# Serializer_DS90UB913A.net
KiCad netlist of a schematic drawn in Altium Designer
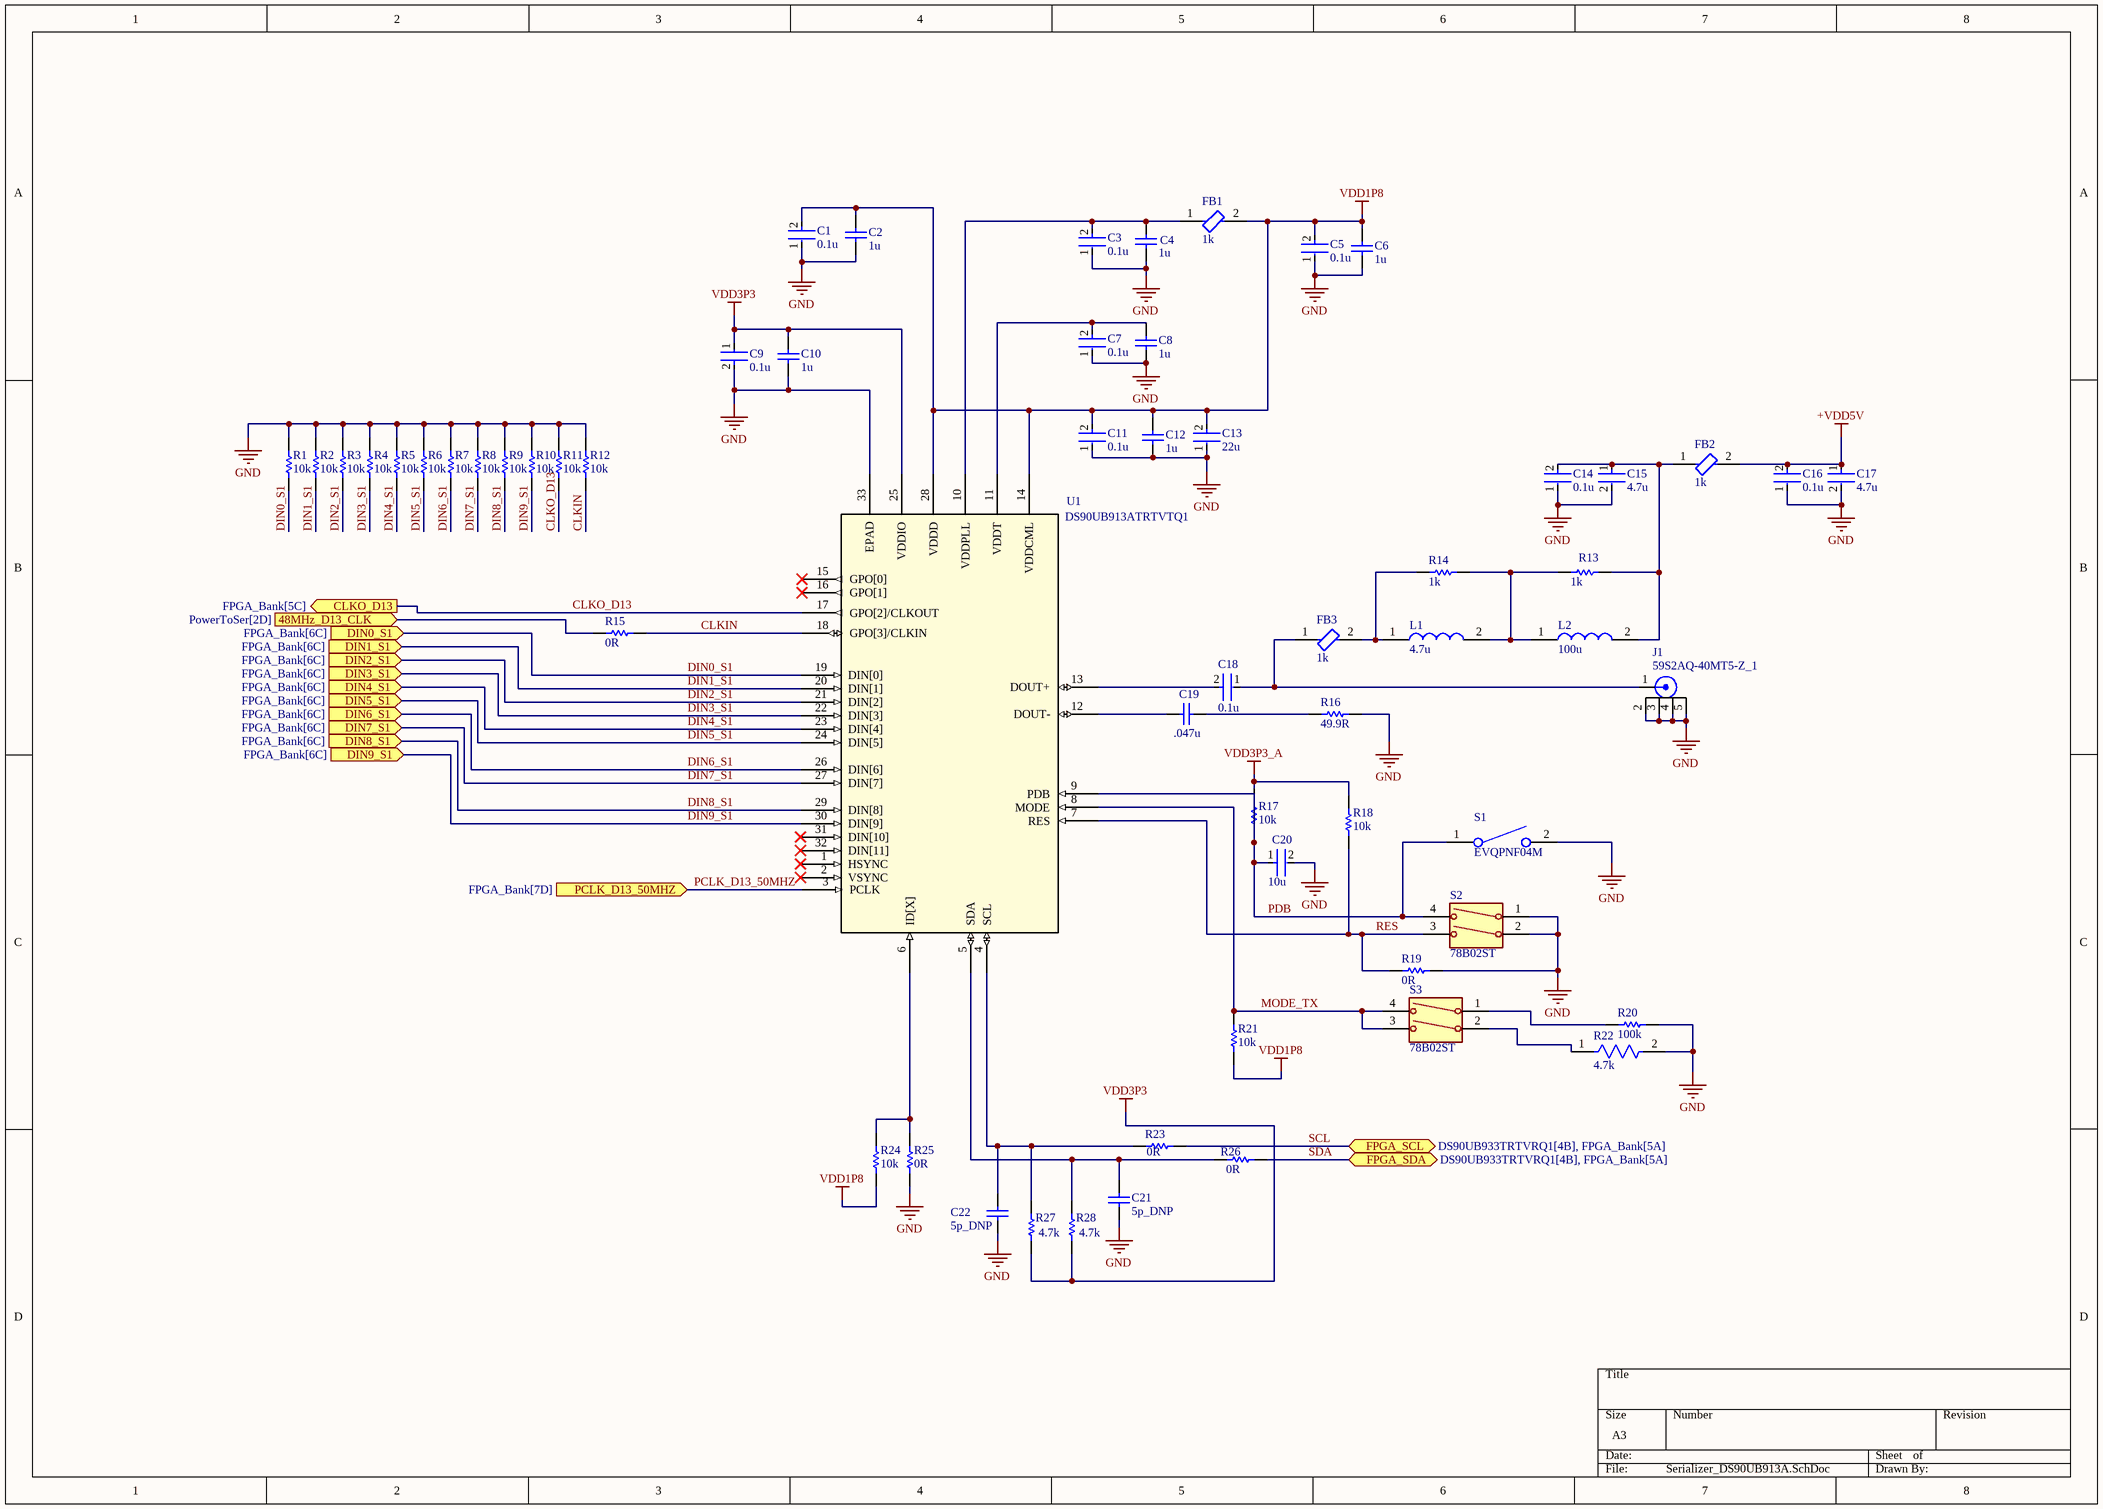
[diagram p0: Serializer_DS90UB913A.SchDoc]

(export (version "E")
  (design (tool "Eeschema 10.0.6"))
  (components
    (comp (ref "C1")
      (value "0.1u")
      (footprint "FP-GRM15-MFG")
      (description "CAP CER 0.1UF 16V X7R 0402")
      (fields (field (name "MANUFACTURER PART NUMBER") "GRM155R71C104KA88D") (field (name "TOLERANCE") "10%"))
      (libsource (lib "Altium Content Vault") (part "236180d848d6139a670b325ea6854c9"))
    )
    (comp (ref "C2")
      (value "1u")
      (footprint "CAPC1608X90X35ML10T15")
      (fields (field (name "MANUFACTURER") "Murata") (field (name "PART NUMBER") "GRM188R71E105KA12D"))
      (libsource (lib "Altium Content Vault") (part "CAP"))
    )
    (comp (ref "C3")
      (value "0.1u")
      (footprint "FP-GRM15-MFG")
      (description "CAP CER 0.1UF 16V X7R 0402")
      (fields (field (name "MANUFACTURER PART NUMBER") "GRM155R71C104KA88D") (field (name "TOLERANCE") "10%"))
      (libsource (lib "Altium Content Vault") (part "236180d848d6139a670b325ea6854c9"))
    )
    (comp (ref "C4")
      (value "1u")
      (footprint "CAPC1608X90X35ML10T15")
      (fields (field (name "MANUFACTURER") "Murata") (field (name "PART NUMBER") "GRM188R71E105KA12D"))
      (libsource (lib "Altium Content Vault") (part "CAP"))
    )
    (comp (ref "C5")
      (value "0.1u")
      (footprint "FP-GRM15-MFG")
      (description "CAP CER 0.1UF 16V X7R 0402")
      (fields (field (name "MANUFACTURER PART NUMBER") "GRM155R71C104KA88D") (field (name "TOLERANCE") "10%"))
      (libsource (lib "Altium Content Vault") (part "236180d848d6139a670b325ea6854c9"))
    )
    (comp (ref "C6")
      (value "1u")
      (footprint "CAPC1608X90X35ML10T15")
      (fields (field (name "MANUFACTURER") "Murata") (field (name "PART NUMBER") "GRM188R71E105KA12D"))
      (libsource (lib "Altium Content Vault") (part "CAP"))
    )
    (comp (ref "C7")
      (value "0.1u")
      (footprint "FP-GRM15-MFG")
      (description "CAP CER 0.1UF 16V X7R 0402")
      (fields (field (name "MANUFACTURER PART NUMBER") "GRM155R71C104KA88D") (field (name "TOLERANCE") "10%"))
      (libsource (lib "Altium Content Vault") (part "236180d848d6139a670b325ea6854c9"))
    )
    (comp (ref "C8")
      (value "1u")
      (footprint "CAPC1608X90X35ML10T15")
      (fields (field (name "MANUFACTURER") "Murata") (field (name "PART NUMBER") "GRM188R71E105KA12D"))
      (libsource (lib "Altium Content Vault") (part "CAP"))
    )
    (comp (ref "C9")
      (value "0.1u")
      (footprint "FP-GRM15-MFG")
      (description "CAP CER 0.1UF 16V X7R 0402")
      (fields (field (name "MANUFACTURER PART NUMBER") "GRM155R71C104KA88D") (field (name "TOLERANCE") "10%"))
      (libsource (lib "Altium Content Vault") (part "236180d848d6139a670b325ea6854c9"))
    )
    (comp (ref "C10")
      (value "1u")
      (footprint "CAPC1608X90X35ML10T15")
      (fields (field (name "MANUFACTURER") "Murata") (field (name "PART NUMBER") "GRM188R71E105KA12D"))
      (libsource (lib "Altium Content Vault") (part "CAP"))
    )
    (comp (ref "C11")
      (value "0.1u")
      (footprint "FP-GRM15-MFG")
      (description "CAP CER 0.1UF 16V X7R 0402")
      (fields (field (name "MANUFACTURER PART NUMBER") "GRM155R71C104KA88D") (field (name "TOLERANCE") "10%"))
      (libsource (lib "Altium Content Vault") (part "236180d848d6139a670b325ea6854c9"))
    )
    (comp (ref "C12")
      (value "1u")
      (footprint "CAPC1608X90X35ML10T15")
      (fields (field (name "MANUFACTURER") "Murata") (field (name "PART NUMBER") "GRM188R71E105KA12D"))
      (libsource (lib "Altium Content Vault") (part "CAP"))
    )
    (comp (ref "C13")
      (value "22u")
      (footprint "FP-GCM32E-0_3-IPC_B")
      (description "Ceramic Capacitor for Automotive 22uF ±10% 16VDC X7R 1210 Embossed T/R")
      (fields (field (name "VOLTAGE") "16V") (field (name "TOLERANCE") "10%"))
      (libsource (lib "Altium Content Vault") (part "f23184f103b6ebe33a8c269c53dcba6"))
    )
    (comp (ref "C14")
      (value "0.1u")
      (footprint "FP-GRM15-MFG")
      (description "CAP CER 0.1UF 16V X7R 0402")
      (fields (field (name "MANUFACTURER PART NUMBER") "GRM155R71C104KA88D") (field (name "TOLERANCE") "10%"))
      (libsource (lib "Altium Content Vault") (part "236180d848d6139a670b325ea6854c9"))
    )
    (comp (ref "C15")
      (value "4.7u")
      (footprint "FP-GRM21B-0_15-MFG")
      (description "CAP CER 4.7UF 16V X7R 0805")
      (fields (field (name "VOLTAGE") "16V") (field (name "TOLERANCE") "10%"))
      (libsource (lib "Altium Content Vault") (part "b4654b650e69147ec39a6b967a45e02"))
    )
    (comp (ref "C16")
      (value "0.1u")
      (footprint "FP-GRM15-MFG")
      (description "CAP CER 0.1UF 16V X7R 0402")
      (fields (field (name "MANUFACTURER PART NUMBER") "GRM155R71C104KA88D") (field (name "TOLERANCE") "10%"))
      (libsource (lib "Altium Content Vault") (part "236180d848d6139a670b325ea6854c9"))
    )
    (comp (ref "C17")
      (value "4.7u")
      (footprint "FP-GRM21B-0_15-MFG")
      (description "CAP CER 4.7UF 16V X7R 0805")
      (fields (field (name "VOLTAGE") "16V") (field (name "TOLERANCE") "10%"))
      (libsource (lib "Altium Content Vault") (part "b4654b650e69147ec39a6b967a45e02"))
    )
    (comp (ref "C18")
      (value "0.1u")
      (footprint "FP-GRM15-MFG")
      (description "CAP CER 0.1UF 16V X7R 0402")
      (fields (field (name "MANUFACTURER PART NUMBER") "GRM155R71C104KA88D") (field (name "TOLERANCE") "10%"))
      (libsource (lib "Altium Content Vault") (part "236180d848d6139a670b325ea6854c9"))
    )
    (comp (ref "C19")
      (value ".047u")
      (footprint "CAPC1608X90X35ML10T15")
      (fields (field (name "MANUFACTURER") "Murata") (field (name "PART NUMBER") "GRM188R71H473KA61D"))
      (libsource (lib "Altium Content Vault") (part "CAP"))
    )
    (comp (ref "C20")
      (value "10u")
      (footprint "FP-GRM21B-0_1-IPC_C")
      (description "Chip Multilayer Ceramic Capacitors for General Purpose, 0805, 10uF, X5R, 15%, 10%, 16V")
      (fields (field (name "TOLERANCE") "10%") (field (name "VOLTAGE") "16V"))
      (libsource (lib "Altium Content Vault") (part "b4654b650e69147ec39a6b967a45e02"))
    )
    (comp (ref "C21")
      (value "5p_DNP")
      (footprint "CAPC1005X55X25LL05T10")
      (fields (field (name "MANUFACTURER") "Murata") (field (name "PART NUMBER") "GRM1555C1H5R0CA01D"))
      (libsource (lib "Altium Content Vault") (part "CAP"))
    )
    (comp (ref "C22")
      (value "5p_DNP")
      (footprint "CAPC1005X55X25LL05T10")
      (fields (field (name "MANUFACTURER") "Murata") (field (name "PART NUMBER") "GRM1555C1H5R0CA01D"))
      (libsource (lib "Altium Content Vault") (part "CAP"))
    )
    (comp (ref "FB1")
      (value "1k")
      (footprint "FP-BLM18-0_15-t0_8-MFG")
      (description "Chip Ferrite Bead, 0603, 1000Ω @ 100MHz, 0.5Ω, 25%, 450mABLM18AG102SN1D")
      (fields (field (name "TOLERANCE") "25%"))
      (libsource (lib "Altium Content Vault") (part "5f30dd21d616792df468990f7003faa"))
    )
    (comp (ref "FB2")
      (value "1k")
      (footprint "FP-BLM18-0_15-t0_8-MFG")
      (description "Chip Ferrite Bead, 0603, 1000Ω @ 100MHz, 0.5Ω, 25%, 450mABLM18AG102SN1D")
      (fields (field (name "TOLERANCE") "25%"))
      (libsource (lib "Altium Content Vault") (part "5f30dd21d616792df468990f7003faa"))
    )
    (comp (ref "FB3")
      (value "1k")
      (footprint "FP-BLM18-0_15-t0_8-MFG")
      (description "Chip Ferrite Bead, 0603, 1000Ω @ 100MHz, 0.5Ω, 25%, 450mABLM18AG102SN1D")
      (fields (field (name "TOLERANCE") "25%"))
      (libsource (lib "Altium Content Vault") (part "5f30dd21d616792df468990f7003faa"))
    )
    (comp (ref "J1")
      (value "59S2AQ-40MT5-Z_1")
      (footprint "SerDes_Eval_Board_Footprints:ROSENBERGER_59S2AQ-40MT5-Z_1")
      (description "RF Connectors / Coaxial Connectors Plug PC-Board SMD Right AngleZWatrBlue")
      (libsource (lib "SerDes_Eval") (part "59S2AQ-40MT5-Z_1"))
    )
    (comp (ref "L1")
      (value "4.7u")
      (footprint "SerDes_Eval_Board_Footprints:1008PS")
      (description "Inductor")
      (fields
        (field (name "MANUFACTURER_PART_NUMBER") "1008PS-472KLB")
        (field (name "MOUSER PART NUMBER") "994-1008PS-472KLB")
      )
      (libsource (lib "SerDes_Eval") (part "1008PS-472KLB"))
    )
    (comp (ref "L2")
      (value "100u")
      (footprint "SerDes_Eval_Board_Footprints:MSS7341T104MLB")
      (description "Inductor")
      (fields
        (field (name "MANUFACTURER_PART_NUMBER") "MSS7341T-104MLD")
        (field (name "MOUSER PART NUMBER") "994-MSS7341T-104MLD")
      )
      (libsource (lib "SerDes_Eval") (part "MSS7341T-104MLB"))
    )
    (comp (ref "R1")
      (value "10k")
      (footprint "RESC1005X40X25ML05T05")
      (fields (field (name "PART NUMBER") "ERJ-2GEJ103X") (field (name "MANUFACTURER") "Panasonic"))
      (libsource (lib "Altium Content Vault") (part "RES"))
    )
    (comp (ref "R2")
      (value "10k")
      (footprint "RESC1005X40X25ML05T05")
      (fields (field (name "PART NUMBER") "ERJ-2GEJ103X") (field (name "MANUFACTURER") "Panasonic"))
      (libsource (lib "Altium Content Vault") (part "RES"))
    )
    (comp (ref "R3")
      (value "10k")
      (footprint "RESC1005X40X25ML05T05")
      (fields (field (name "PART NUMBER") "ERJ-2GEJ103X") (field (name "MANUFACTURER") "Panasonic"))
      (libsource (lib "Altium Content Vault") (part "RES"))
    )
    (comp (ref "R4")
      (value "10k")
      (footprint "RESC1005X40X25ML05T05")
      (fields (field (name "PART NUMBER") "ERJ-2GEJ103X") (field (name "MANUFACTURER") "Panasonic"))
      (libsource (lib "Altium Content Vault") (part "RES"))
    )
    (comp (ref "R5")
      (value "10k")
      (footprint "RESC1005X40X25ML05T05")
      (fields (field (name "PART NUMBER") "ERJ-2GEJ103X") (field (name "MANUFACTURER") "Panasonic"))
      (libsource (lib "Altium Content Vault") (part "RES"))
    )
    (comp (ref "R6")
      (value "10k")
      (footprint "RESC1005X40X25ML05T05")
      (fields (field (name "PART NUMBER") "ERJ-2GEJ103X") (field (name "MANUFACTURER") "Panasonic"))
      (libsource (lib "Altium Content Vault") (part "RES"))
    )
    (comp (ref "R7")
      (value "10k")
      (footprint "RESC1005X40X25ML05T05")
      (fields (field (name "PART NUMBER") "ERJ-2GEJ103X") (field (name "MANUFACTURER") "Panasonic"))
      (libsource (lib "Altium Content Vault") (part "RES"))
    )
    (comp (ref "R8")
      (value "10k")
      (footprint "RESC1005X40X25ML05T05")
      (fields (field (name "PART NUMBER") "ERJ-2GEJ103X") (field (name "MANUFACTURER") "Panasonic"))
      (libsource (lib "Altium Content Vault") (part "RES"))
    )
    (comp (ref "R9")
      (value "10k")
      (footprint "RESC1005X40X25ML05T05")
      (fields (field (name "PART NUMBER") "ERJ-2GEJ103X") (field (name "MANUFACTURER") "Panasonic"))
      (libsource (lib "Altium Content Vault") (part "RES"))
    )
    (comp (ref "R10")
      (value "10k")
      (footprint "RESC1005X40X25ML05T05")
      (fields (field (name "PART NUMBER") "ERJ-2GEJ103X") (field (name "MANUFACTURER") "Panasonic"))
      (libsource (lib "Altium Content Vault") (part "RES"))
    )
    (comp (ref "R11")
      (value "10k")
      (footprint "RESC1005X40X25ML05T05")
      (fields (field (name "PART NUMBER") "ERJ-2GEJ103X") (field (name "MANUFACTURER") "Panasonic"))
      (libsource (lib "Altium Content Vault") (part "RES"))
    )
    (comp (ref "R12")
      (value "10k")
      (footprint "RESC1005X40X25ML05T05")
      (fields (field (name "PART NUMBER") "ERJ-2GEJ103X") (field (name "MANUFACTURER") "Panasonic"))
      (libsource (lib "Altium Content Vault") (part "RES"))
    )
    (comp (ref "R13")
      (value "1k")
      (footprint "RESC1608X55X30LL15T15")
      (fields (field (name "PART NUMBER") "ERJ-3EKF1001V") (field (name "MANUFACTURER") "Panasonic"))
      (libsource (lib "Altium Content Vault") (part "RES"))
    )
    (comp (ref "R14")
      (value "1k")
      (footprint "RESC1608X55X30LL15T15")
      (fields (field (name "PART NUMBER") "ERJ-3EKF1001V") (field (name "MANUFACTURER") "Panasonic"))
      (libsource (lib "Altium Content Vault") (part "RES"))
    )
    (comp (ref "R15")
      (value "0R")
      (footprint "RESC1005X40X25LL05T05")
      (description "Chip Resistor, 0 Ohm, 0.1 W, -55 to 155 degC, 0402 (1005 Metric), RoHS, Tape and Reel")
      (fields (field (name "MANUFACTURER") "Panasonic") (field (name "TOLERANCE") "5%"))
      (libsource (lib "Altium Content Vault") (part "RES-2"))
    )
    (comp (ref "R16")
      (value "49.9R")
      (footprint "RESC1608X55X30ML15T15")
      (fields (field (name "MANUFACTURER") "Panasonic") (field (name "PART NUMBER") "ERJ-3EKF49R9V"))
      (libsource (lib "Altium Content Vault") (part "RES"))
    )
    (comp (ref "R17")
      (value "10k")
      (footprint "RESC1005X40X25ML05T05")
      (fields (field (name "PART NUMBER") "ERJ-2GEJ103X") (field (name "MANUFACTURER") "Panasonic"))
      (libsource (lib "Altium Content Vault") (part "RES"))
    )
    (comp (ref "R18")
      (value "10k")
      (footprint "RESC1005X40X25ML05T05")
      (fields (field (name "PART NUMBER") "ERJ-2GEJ103X") (field (name "MANUFACTURER") "Panasonic"))
      (libsource (lib "Altium Content Vault") (part "RES"))
    )
    (comp (ref "R19")
      (value "0R")
      (footprint "RESC1005X40X25LL05T05")
      (description "Chip Resistor, 0 Ohm, 0.1 W, -55 to 155 degC, 0402 (1005 Metric), RoHS, Tape and Reel")
      (fields (field (name "MANUFACTURER") "Panasonic") (field (name "TOLERANCE") "5%"))
      (libsource (lib "Altium Content Vault") (part "RES-2"))
    )
    (comp (ref "R20")
      (value "100k")
      (footprint "RESC2013X70X40ML20T20")
      (fields (field (name "PART NUMBER") "ERJ-6ENF1003V") (field (name "MANUFACTURER") "Panasonic"))
      (libsource (lib "Altium Content Vault") (part "RES"))
    )
    (comp (ref "R21")
      (value "10k")
      (footprint "RESC1005X40X25ML05T05")
      (fields (field (name "PART NUMBER") "ERJ-2GEJ103X") (field (name "MANUFACTURER") "Panasonic"))
      (libsource (lib "Altium Content Vault") (part "RES"))
    )
    (comp (ref "R22")
      (value "4.7k")
      (footprint "FP-ERJ6GE-MFG")
      (description "RES SMD 4.7K OHM 5% 1/8W 0805")
      (fields (field (name "TOLERANCE") "5%"))
      (libsource (lib "Altium Content Vault") (part "1029c3af85768c4190bb7ad29bc67b5"))
    )
    (comp (ref "R23")
      (value "0R")
      (footprint "RESC1005X40X25LL05T05")
      (description "Chip Resistor, 0 Ohm, 0.1 W, -55 to 155 degC, 0402 (1005 Metric), RoHS, Tape and Reel")
      (fields (field (name "MANUFACTURER") "Panasonic") (field (name "TOLERANCE") "5%"))
      (libsource (lib "Altium Content Vault") (part "RES-2"))
    )
    (comp (ref "R24")
      (value "10k")
      (footprint "RESC1005X40X25ML05T05")
      (fields (field (name "PART NUMBER") "ERJ-2GEJ103X") (field (name "MANUFACTURER") "Panasonic"))
      (libsource (lib "Altium Content Vault") (part "RES"))
    )
    (comp (ref "R25")
      (value "0R")
      (footprint "RESC1005X40X25LL05T05")
      (description "Chip Resistor, 0 Ohm, 0.1 W, -55 to 155 degC, 0402 (1005 Metric), RoHS, Tape and Reel")
      (fields (field (name "MANUFACTURER") "Panasonic") (field (name "TOLERANCE") "5%"))
      (libsource (lib "Altium Content Vault") (part "RES-2"))
    )
    (comp (ref "R26")
      (value "0R")
      (footprint "RESC1005X40X25LL05T05")
      (description "Chip Resistor, 0 Ohm, 0.1 W, -55 to 155 degC, 0402 (1005 Metric), RoHS, Tape and Reel")
      (fields (field (name "MANUFACTURER") "Panasonic") (field (name "TOLERANCE") "5%"))
      (libsource (lib "Altium Content Vault") (part "RES-2"))
    )
    (comp (ref "R27")
      (value "4.7k")
      (footprint "RESC1005X40X25LL05T05")
      (description "Chip Resistor, 4.7 KOhm, +/- 1%, 0.1 W, -55 to 155 degC, 0402 (1005 Metric), RoHS, Tape and Reel")
      (fields (field (name "TOLERANCE") "1%") (field (name "PARTNUMBER") "ERJ-2RKF4701X"))
      (libsource (lib "Altium Content Vault") (part "RES-2"))
    )
    (comp (ref "R28")
      (value "4.7k")
      (footprint "RESC1005X40X25LL05T05")
      (description "Chip Resistor, 4.7 KOhm, +/- 1%, 0.1 W, -55 to 155 degC, 0402 (1005 Metric), RoHS, Tape and Reel")
      (fields (field (name "TOLERANCE") "1%") (field (name "PARTNUMBER") "ERJ-2RKF4701X"))
      (libsource (lib "Altium Content Vault") (part "RES-2"))
    )
    (comp (ref "S1")
      (value "EVQPNF04M")
      (footprint "SamacSys:EVQ5PN05K")
      (description "Switch")
      (libsource (lib "SerDes_Eval") (part "EVQPNF04M"))
    )
    (comp (ref "S2")
      (value "78B02ST")
      (footprint "78B02ST")
      (description "PCB Slide Switch Single Pole Single Throw (SPST) 150 mA Slide")
      (fields (field (name "MOUSER PART NUMBER") "706-78B02ST"))
      (libsource (lib "SerDes_Eval") (part "78B02ST"))
    )
    (comp (ref "S3")
      (value "78B02ST")
      (footprint "78B02ST")
      (description "PCB Slide Switch Single Pole Single Throw (SPST) 150 mA Slide")
      (fields (field (name "MOUSER PART NUMBER") "706-78B02ST"))
      (libsource (lib "SerDes_Eval") (part "78B02ST"))
    )
    (comp (ref "U1")
      (value "DS90UB913ATRTVTQ1")
      (footprint "RTV32_3P1X3P1_TEX")
      (description "25- to 100-MHz, 10-bit & 12-bit FPD-Link III serializer 32-WQFN -40 to 105")
      (fields (field (name "COPYRIGHT") "Copyright (C) 2025 Ultra Librarian. All rights reserved."))
      (libsource (lib "SerDes_Eval") (part "DS90UB913ATRTVTQ1"))
    )
  )
  (nets
    (net (code "1") (name "+VDD5V") (class "Default")
      (node (ref "C16") (pin "2") (pinfunction "2_2") (pintype "passive"))
      (node (ref "C17") (pin "1") (pinfunction "1_1") (pintype "passive"))
      (node (ref "FB2") (pin "2") (pinfunction "2_2") (pintype "passive"))
    )
    (net (code "2") (name "/48MHz_D13_CLK") (class "Default")
      (node (ref "R15") (pin "2") (pinfunction "2_2") (pintype "passive"))
    )
    (net (code "3") (name "/CLKIN") (class "Default")
      (node (ref "R12") (pin "1") (pinfunction "1_1") (pintype "passive"))
      (node (ref "R15") (pin "1") (pinfunction "1_1") (pintype "passive"))
      (node (ref "U1") (pin "18") (pinfunction "GPO[3]/CLKIN_18") (pintype "bidirectional"))
    )
    (net (code "4") (name "/CLKO_D13") (class "Default")
      (node (ref "R11") (pin "1") (pinfunction "1_1") (pintype "passive"))
      (node (ref "U1") (pin "17") (pinfunction "GPO[2]/CLKOUT_17") (pintype "output"))
    )
    (net (code "5") (name "/DIN0_S1") (class "Default")
      (node (ref "R1") (pin "1") (pinfunction "1_1") (pintype "passive"))
      (node (ref "U1") (pin "19") (pinfunction "DIN[0]_19") (pintype "input"))
    )
    (net (code "6") (name "/DIN1_S1") (class "Default")
      (node (ref "R2") (pin "1") (pinfunction "1_1") (pintype "passive"))
      (node (ref "U1") (pin "20") (pinfunction "DIN[1]_20") (pintype "input"))
    )
    (net (code "7") (name "/DIN2_S1") (class "Default")
      (node (ref "R3") (pin "1") (pinfunction "1_1") (pintype "passive"))
      (node (ref "U1") (pin "21") (pinfunction "DIN[2]_21") (pintype "input"))
    )
    (net (code "8") (name "/DIN3_S1") (class "Default")
      (node (ref "R4") (pin "1") (pinfunction "1_1") (pintype "passive"))
      (node (ref "U1") (pin "22") (pinfunction "DIN[3]_22") (pintype "input"))
    )
    (net (code "9") (name "/DIN4_S1") (class "Default")
      (node (ref "R5") (pin "1") (pinfunction "1_1") (pintype "passive"))
      (node (ref "U1") (pin "23") (pinfunction "DIN[4]_23") (pintype "input"))
    )
    (net (code "10") (name "/DIN5_S1") (class "Default")
      (node (ref "R6") (pin "1") (pinfunction "1_1") (pintype "passive"))
      (node (ref "U1") (pin "24") (pinfunction "DIN[5]_24") (pintype "input"))
    )
    (net (code "11") (name "/DIN6_S1") (class "Default")
      (node (ref "R7") (pin "1") (pinfunction "1_1") (pintype "passive"))
      (node (ref "U1") (pin "26") (pinfunction "DIN[6]_26") (pintype "input"))
    )
    (net (code "12") (name "/DIN7_S1") (class "Default")
      (node (ref "R8") (pin "1") (pinfunction "1_1") (pintype "passive"))
      (node (ref "U1") (pin "27") (pinfunction "DIN[7]_27") (pintype "input"))
    )
    (net (code "13") (name "/DIN8_S1") (class "Default")
      (node (ref "R9") (pin "1") (pinfunction "1_1") (pintype "passive"))
      (node (ref "U1") (pin "29") (pinfunction "DIN[8]_29") (pintype "input"))
    )
    (net (code "14") (name "/DIN9_S1") (class "Default")
      (node (ref "R10") (pin "1") (pinfunction "1_1") (pintype "passive"))
      (node (ref "U1") (pin "30") (pinfunction "DIN[9]_30") (pintype "input"))
    )
    (net (code "15") (name "/MODE_TX") (class "Default")
      (node (ref "R21") (pin "2") (pinfunction "2_2") (pintype "passive"))
      (node (ref "S3") (pin "3") (pinfunction "COM_2_3") (pintype "passive"))
      (node (ref "S3") (pin "4") (pinfunction "NO_2_4") (pintype "passive"))
      (node (ref "U1") (pin "8") (pinfunction "MODE_8") (pintype "input"))
    )
    (net (code "16") (name "/PCLK_D13_50MHZ") (class "Default")
      (node (ref "U1") (pin "3") (pinfunction "PCLK_3") (pintype "input"))
    )
    (net (code "17") (name "/PDB") (class "Default")
      (node (ref "C20") (pin "1") (pinfunction "1_1") (pintype "passive"))
      (node (ref "R17") (pin "1") (pinfunction "1_1") (pintype "passive"))
      (node (ref "S1") (pin "1") (pinfunction "COM_1") (pintype "passive"))
      (node (ref "S2") (pin "4") (pinfunction "NO_2_4") (pintype "passive"))
      (node (ref "U1") (pin "9") (pinfunction "PDB_9") (pintype "input"))
    )
    (net (code "18") (name "/RES") (class "Default")
      (node (ref "R18") (pin "1") (pinfunction "1_1") (pintype "passive"))
      (node (ref "R19") (pin "2") (pinfunction "2_2") (pintype "passive"))
      (node (ref "S2") (pin "3") (pinfunction "COM_2_3") (pintype "passive"))
      (node (ref "U1") (pin "7") (pinfunction "RES_7") (pintype "input"))
    )
    (net (code "19") (name "/SCL") (class "Default")
      (node (ref "R23") (pin "1") (pinfunction "1_1") (pintype "passive"))
    )
    (net (code "20") (name "/SDA") (class "Default")
      (node (ref "R26") (pin "1") (pinfunction "1_1") (pintype "passive"))
    )
    (net (code "21") (name "GND") (class "Default")
      (node (ref "C1") (pin "1") (pinfunction "1_1") (pintype "passive"))
      (node (ref "C10") (pin "1") (pinfunction "1_1") (pintype "passive"))
      (node (ref "C11") (pin "1") (pinfunction "1_1") (pintype "passive"))
      (node (ref "C12") (pin "1") (pinfunction "1_1") (pintype "passive"))
      (node (ref "C13") (pin "1") (pinfunction "1_1") (pintype "passive"))
      (node (ref "C14") (pin "1") (pinfunction "1_1") (pintype "passive"))
      (node (ref "C15") (pin "2") (pinfunction "2_2") (pintype "passive"))
      (node (ref "C16") (pin "1") (pinfunction "1_1") (pintype "passive"))
      (node (ref "C17") (pin "2") (pinfunction "2_2") (pintype "passive"))
      (node (ref "C2") (pin "1") (pinfunction "1_1") (pintype "passive"))
      (node (ref "C20") (pin "2") (pinfunction "2_2") (pintype "passive"))
      (node (ref "C21") (pin "1") (pinfunction "1_1") (pintype "passive"))
      (node (ref "C22") (pin "1") (pinfunction "1_1") (pintype "passive"))
      (node (ref "C3") (pin "1") (pinfunction "1_1") (pintype "passive"))
      (node (ref "C4") (pin "1") (pinfunction "1_1") (pintype "passive"))
      (node (ref "C5") (pin "1") (pinfunction "1_1") (pintype "passive"))
      (node (ref "C6") (pin "1") (pinfunction "1_1") (pintype "passive"))
      (node (ref "C7") (pin "1") (pinfunction "1_1") (pintype "passive"))
      (node (ref "C8") (pin "1") (pinfunction "1_1") (pintype "passive"))
      (node (ref "C9") (pin "2") (pinfunction "2_2") (pintype "passive"))
      (node (ref "J1") (pin "2") (pinfunction "2_2") (pintype "passive"))
      (node (ref "J1") (pin "3") (pinfunction "3_3") (pintype "passive"))
      (node (ref "J1") (pin "4") (pinfunction "4_4") (pintype "passive"))
      (node (ref "J1") (pin "5") (pinfunction "5_5") (pintype "passive"))
      (node (ref "R1") (pin "2") (pinfunction "2_2") (pintype "passive"))
      (node (ref "R10") (pin "2") (pinfunction "2_2") (pintype "passive"))
      (node (ref "R11") (pin "2") (pinfunction "2_2") (pintype "passive"))
      (node (ref "R12") (pin "2") (pinfunction "2_2") (pintype "passive"))
      (node (ref "R16") (pin "2") (pinfunction "2_2") (pintype "passive"))
      (node (ref "R19") (pin "1") (pinfunction "1_1") (pintype "passive"))
      (node (ref "R2") (pin "2") (pinfunction "2_2") (pintype "passive"))
      (node (ref "R20") (pin "2") (pinfunction "2_2") (pintype "passive"))
      (node (ref "R22") (pin "2") (pinfunction "2_2") (pintype "passive"))
      (node (ref "R25") (pin "1") (pinfunction "1_1") (pintype "passive"))
      (node (ref "R3") (pin "2") (pinfunction "2_2") (pintype "passive"))
      (node (ref "R4") (pin "2") (pinfunction "2_2") (pintype "passive"))
      (node (ref "R5") (pin "2") (pinfunction "2_2") (pintype "passive"))
      (node (ref "R6") (pin "2") (pinfunction "2_2") (pintype "passive"))
      (node (ref "R7") (pin "2") (pinfunction "2_2") (pintype "passive"))
      (node (ref "R8") (pin "2") (pinfunction "2_2") (pintype "passive"))
      (node (ref "R9") (pin "2") (pinfunction "2_2") (pintype "passive"))
      (node (ref "S1") (pin "2") (pinfunction "NO_2") (pintype "passive"))
      (node (ref "S2") (pin "1") (pinfunction "COM_1_1") (pintype "passive"))
      (node (ref "S2") (pin "2") (pinfunction "NO_1_2") (pintype "passive"))
      (node (ref "U1") (pin "33") (pinfunction "EPAD_33") (pintype "passive"))
    )
    (net (code "22") (name "Net-(C14-Pad2)") (class "Default")
      (node (ref "C14") (pin "2") (pinfunction "2_2") (pintype "passive"))
      (node (ref "C15") (pin "1") (pinfunction "1_1") (pintype "passive"))
      (node (ref "FB2") (pin "1") (pinfunction "1_1") (pintype "passive"))
      (node (ref "L2") (pin "2") (pinfunction "2_2") (pintype "passive"))
      (node (ref "R13") (pin "2") (pinfunction "2_2") (pintype "passive"))
    )
    (net (code "23") (name "Net-(C18-Pad1)") (class "Default")
      (node (ref "C18") (pin "1") (pinfunction "1_1") (pintype "passive"))
      (node (ref "FB3") (pin "1") (pinfunction "1_1") (pintype "passive"))
      (node (ref "J1") (pin "1") (pinfunction "1_1") (pintype "passive"))
    )
    (net (code "24") (name "Net-(C19-Pad2)") (class "Default")
      (node (ref "C19") (pin "2") (pinfunction "2_2") (pintype "passive"))
      (node (ref "R16") (pin "1") (pinfunction "1_1") (pintype "passive"))
    )
    (net (code "25") (name "Net-(FB3-Pad2)") (class "Default")
      (node (ref "FB3") (pin "2") (pinfunction "2_2") (pintype "passive"))
      (node (ref "L1") (pin "1") (pinfunction "1_1") (pintype "passive"))
      (node (ref "R14") (pin "1") (pinfunction "1_1") (pintype "passive"))
    )
    (net (code "26") (name "Net-(L1-Pad2)") (class "Default")
      (node (ref "L1") (pin "2") (pinfunction "2_2") (pintype "passive"))
      (node (ref "L2") (pin "1") (pinfunction "1_1") (pintype "passive"))
      (node (ref "R13") (pin "1") (pinfunction "1_1") (pintype "passive"))
      (node (ref "R14") (pin "2") (pinfunction "2_2") (pintype "passive"))
    )
    (net (code "27") (name "Net-(S3-COM_1)") (class "Default")
      (node (ref "R20") (pin "1") (pinfunction "1_1") (pintype "passive"))
      (node (ref "S3") (pin "1") (pinfunction "COM_1_1") (pintype "passive"))
    )
    (net (code "28") (name "Net-(S3-NO_1)") (class "Default")
      (node (ref "R22") (pin "1") (pinfunction "1_1") (pintype "passive"))
      (node (ref "S3") (pin "2") (pinfunction "NO_1_2") (pintype "passive"))
    )
    (net (code "29") (name "Net-(U1-DOUT+)") (class "Default")
      (node (ref "C18") (pin "2") (pinfunction "2_2") (pintype "passive"))
      (node (ref "U1") (pin "13") (pinfunction "DOUT+_13") (pintype "bidirectional"))
    )
    (net (code "30") (name "Net-(U1-DOUT-)") (class "Default")
      (node (ref "C19") (pin "1") (pinfunction "1_1") (pintype "passive"))
      (node (ref "U1") (pin "12") (pinfunction "DOUT-_12") (pintype "bidirectional"))
    )
    (net (code "31") (name "Net-(U1-ID[X])") (class "Default")
      (node (ref "R24") (pin "2") (pinfunction "2_2") (pintype "passive"))
      (node (ref "R25") (pin "2") (pinfunction "2_2") (pintype "passive"))
      (node (ref "U1") (pin "6") (pinfunction "ID[X]_6") (pintype "input"))
    )
    (net (code "32") (name "Net-(U1-SCL)") (class "Default")
      (node (ref "C22") (pin "2") (pinfunction "2_2") (pintype "passive"))
      (node (ref "R23") (pin "2") (pinfunction "2_2") (pintype "passive"))
      (node (ref "R27") (pin "2") (pinfunction "2_2") (pintype "passive"))
      (node (ref "U1") (pin "4") (pinfunction "SCL_4") (pintype "bidirectional"))
    )
    (net (code "33") (name "Net-(U1-SDA)") (class "Default")
      (node (ref "C21") (pin "2") (pinfunction "2_2") (pintype "passive"))
      (node (ref "R26") (pin "2") (pinfunction "2_2") (pintype "passive"))
      (node (ref "R28") (pin "2") (pinfunction "2_2") (pintype "passive"))
      (node (ref "U1") (pin "5") (pinfunction "SDA_5") (pintype "bidirectional"))
    )
    (net (code "34") (name "Net-(U1-VDDPLL)") (class "Default")
      (node (ref "C3") (pin "2") (pinfunction "2_2") (pintype "passive"))
      (node (ref "C4") (pin "2") (pinfunction "2_2") (pintype "passive"))
      (node (ref "FB1") (pin "1") (pinfunction "1_1") (pintype "passive"))
      (node (ref "U1") (pin "10") (pinfunction "VDDPLL_10") (pintype "power_in"))
    )
    (net (code "35") (name "Net-(U1-VDDT)") (class "Default")
      (node (ref "C7") (pin "2") (pinfunction "2_2") (pintype "passive"))
      (node (ref "C8") (pin "2") (pinfunction "2_2") (pintype "passive"))
      (node (ref "U1") (pin "11") (pinfunction "VDDT_11") (pintype "power_in"))
    )
    (net (code "36") (name "VDD1P8") (class "Default")
      (node (ref "C1") (pin "2") (pinfunction "2_2") (pintype "passive"))
      (node (ref "C11") (pin "2") (pinfunction "2_2") (pintype "passive"))
      (node (ref "C12") (pin "2") (pinfunction "2_2") (pintype "passive"))
      (node (ref "C13") (pin "2") (pinfunction "2_2") (pintype "passive"))
      (node (ref "C2") (pin "2") (pinfunction "2_2") (pintype "passive"))
      (node (ref "C5") (pin "2") (pinfunction "2_2") (pintype "passive"))
      (node (ref "C6") (pin "2") (pinfunction "2_2") (pintype "passive"))
      (node (ref "FB1") (pin "2") (pinfunction "2_2") (pintype "passive"))
      (node (ref "R21") (pin "1") (pinfunction "1_1") (pintype "passive"))
      (node (ref "R24") (pin "1") (pinfunction "1_1") (pintype "passive"))
      (node (ref "U1") (pin "14") (pinfunction "VDDCML_14") (pintype "power_in"))
      (node (ref "U1") (pin "28") (pinfunction "VDDD_28") (pintype "power_in"))
    )
    (net (code "37") (name "VDD3P3") (class "Default")
      (node (ref "C10") (pin "2") (pinfunction "2_2") (pintype "passive"))
      (node (ref "C9") (pin "1") (pinfunction "1_1") (pintype "passive"))
      (node (ref "R27") (pin "1") (pinfunction "1_1") (pintype "passive"))
      (node (ref "R28") (pin "1") (pinfunction "1_1") (pintype "passive"))
      (node (ref "U1") (pin "25") (pinfunction "VDDIO_25") (pintype "power_in"))
    )
    (net (code "38") (name "VDD3P3_A") (class "Default")
      (node (ref "R17") (pin "2") (pinfunction "2_2") (pintype "passive"))
      (node (ref "R18") (pin "2") (pinfunction "2_2") (pintype "passive"))
    )
    (net (code "39") (name "unconnected-(U1-DIN[10]-Pad31)") (class "Default")
      (node (ref "U1") (pin "31") (pinfunction "DIN[10]_31") (pintype "input+no_connect"))
    )
    (net (code "40") (name "unconnected-(U1-DIN[11]-Pad32)") (class "Default")
      (node (ref "U1") (pin "32") (pinfunction "DIN[11]_32") (pintype "input+no_connect"))
    )
    (net (code "41") (name "unconnected-(U1-GPO[0]-Pad15)") (class "Default")
      (node (ref "U1") (pin "15") (pinfunction "GPO[0]_15") (pintype "output+no_connect"))
    )
    (net (code "42") (name "unconnected-(U1-GPO[1]-Pad16)") (class "Default")
      (node (ref "U1") (pin "16") (pinfunction "GPO[1]_16") (pintype "output+no_connect"))
    )
    (net (code "43") (name "unconnected-(U1-HSYNC-Pad1)") (class "Default")
      (node (ref "U1") (pin "1") (pinfunction "HSYNC_1") (pintype "input+no_connect"))
    )
    (net (code "44") (name "unconnected-(U1-VSYNC-Pad2)") (class "Default")
      (node (ref "U1") (pin "2") (pinfunction "VSYNC_2") (pintype "input+no_connect"))
    )
  )
)
